# NightLight.net
KiCad netlist of a schematic drawn in EAGLE
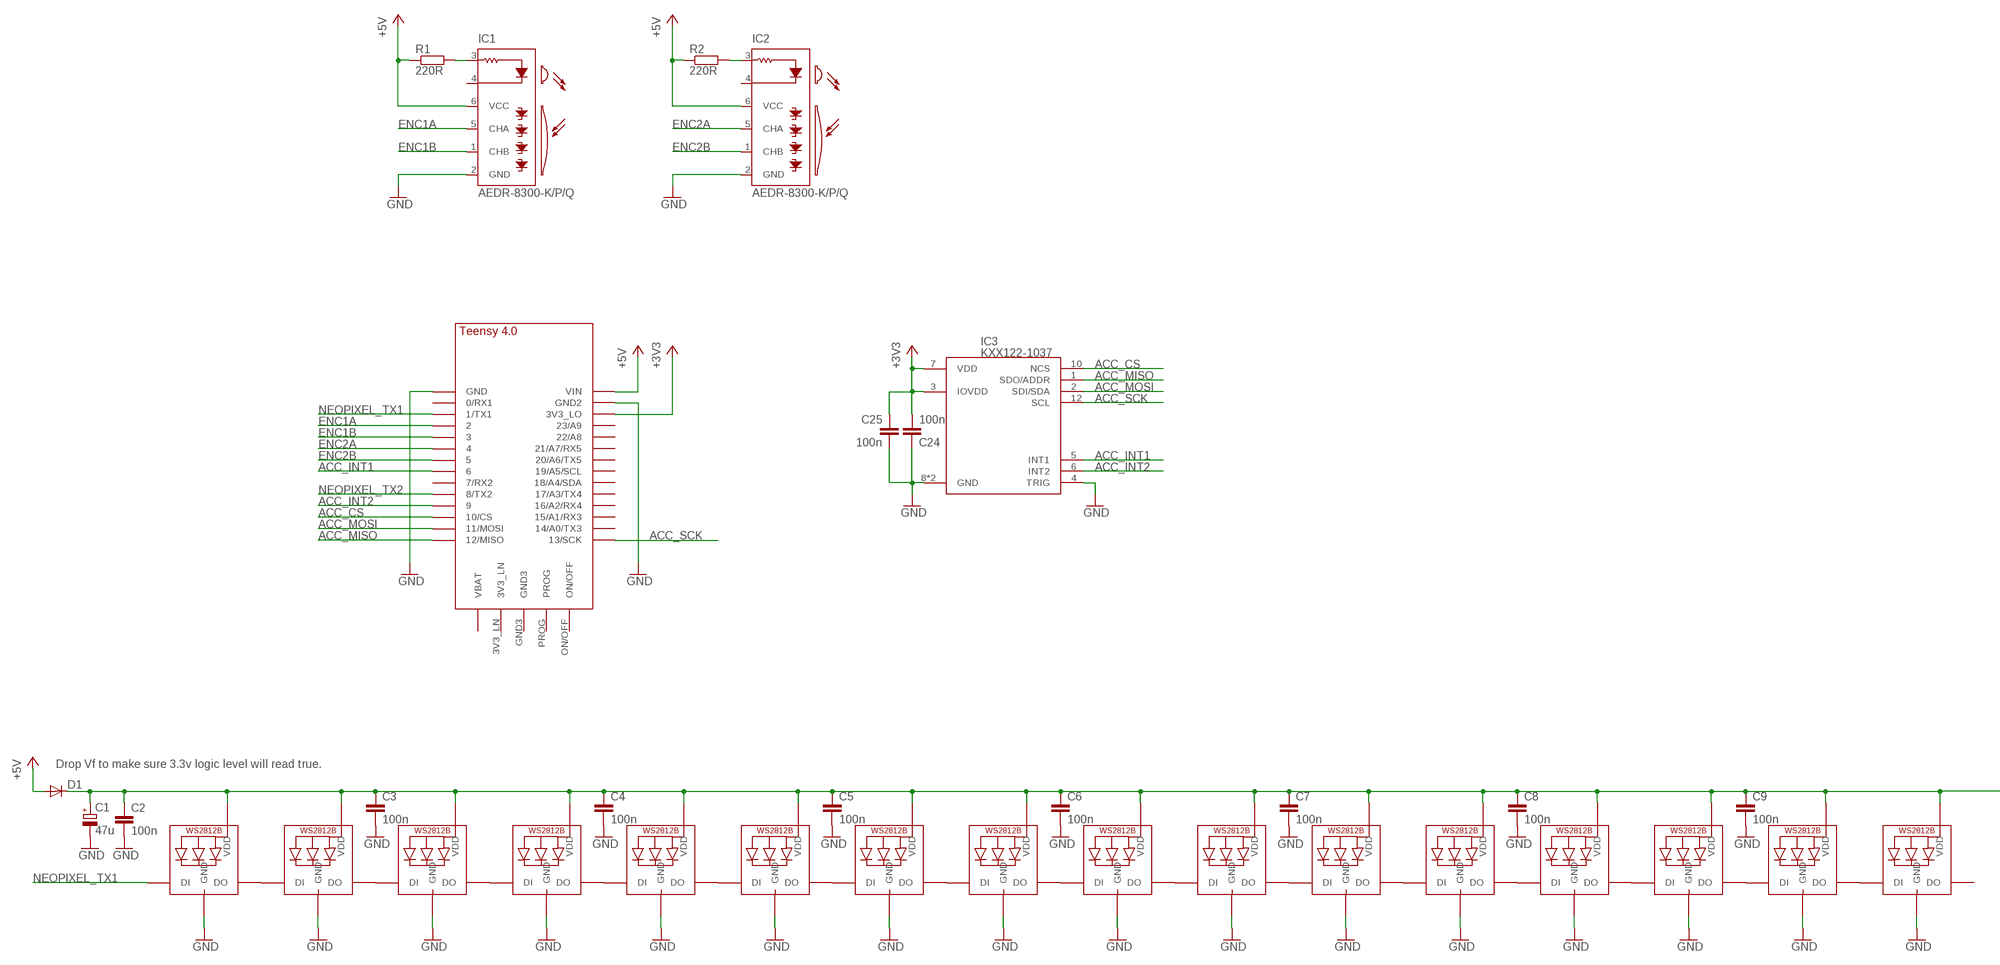
[diagram p0: schematic, sheet 1, part 1 of 2]
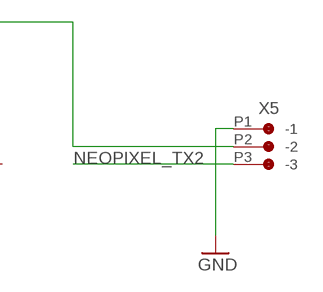
[diagram p1: schematic, sheet 1, part 2 of 2]

(export (version "E")
  (design (tool "Eeschema 10.0.6"))
  (components
    (comp (ref "C1")
      (value "47u")
      (footprint "eagle-import:CPOL-5")
      (libsource (lib "eagle-import") (part "CPOL-EU153CLV-0505"))
    )
    (comp (ref "C2")
      (value "100n")
      (footprint "eagle-import:C0603")
      (libsource (lib "eagle-import") (part "Rebel_15457297_C-EUC0603"))
    )
    (comp (ref "C3")
      (value "100n")
      (footprint "eagle-import:C0603")
      (libsource (lib "eagle-import") (part "Rebel_15457297_C-EUC0603"))
    )
    (comp (ref "C4")
      (value "100n")
      (footprint "eagle-import:C0603")
      (libsource (lib "eagle-import") (part "Rebel_15457297_C-EUC0603"))
    )
    (comp (ref "C5")
      (value "100n")
      (footprint "eagle-import:C0603")
      (libsource (lib "eagle-import") (part "Rebel_15457297_C-EUC0603"))
    )
    (comp (ref "C6")
      (value "100n")
      (footprint "eagle-import:C0603")
      (libsource (lib "eagle-import") (part "Rebel_15457297_C-EUC0603"))
    )
    (comp (ref "C7")
      (value "100n")
      (footprint "eagle-import:C0603")
      (libsource (lib "eagle-import") (part "Rebel_15457297_C-EUC0603"))
    )
    (comp (ref "C8")
      (value "100n")
      (footprint "eagle-import:C0603")
      (libsource (lib "eagle-import") (part "Rebel_15457297_C-EUC0603"))
    )
    (comp (ref "C9")
      (value "100n")
      (footprint "eagle-import:C0603")
      (libsource (lib "eagle-import") (part "Rebel_15457297_C-EUC0603"))
    )
    (comp (ref "C24")
      (value "100n")
      (footprint "eagle-import:C0603")
      (libsource (lib "eagle-import") (part "C-EUC0603"))
    )
    (comp (ref "C25")
      (value "100n")
      (footprint "eagle-import:C0603")
      (libsource (lib "eagle-import") (part "C-EUC0603"))
    )
    (comp (ref "D1")
      (value "DIODE1N4001")
      (footprint "eagle-import:DIODE-1N4001")
      (libsource (lib "eagle-import") (part "DIODE1N4001"))
    )
    (comp (ref "IC1")
      (value "AEDR-8300-K/P/Q")
      (footprint "eagle-import:AEDR-8300")
      (fields (field (name "MF") "AGILENT TECHNOLOGIES") (field (name "MPN") "AEDR-8300-1P2"))
      (libsource (lib "eagle-import") (part "AEDR-8300-K/P/Q"))
    )
    (comp (ref "IC2")
      (value "AEDR-8300-K/P/Q")
      (footprint "eagle-import:AEDR-8300")
      (fields (field (name "MF") "AGILENT TECHNOLOGIES") (field (name "MPN") "AEDR-8300-1P2"))
      (libsource (lib "eagle-import") (part "AEDR-8300-K/P/Q"))
    )
    (comp (ref "IC3")
      (value "KXX122-1037")
      (footprint "eagle-import:LGA16R50P4X4_200X200X100")
      (libsource (lib "eagle-import") (part "KXX122-1037"))
    )
    (comp (ref "LED1")
      (value "WS2812B5050")
      (footprint "eagle-import:WS2812B")
      (libsource (lib "eagle-import") (part "WS2812B5050"))
    )
    (comp (ref "LED2")
      (value "WS2812B5050")
      (footprint "eagle-import:WS2812B")
      (libsource (lib "eagle-import") (part "WS2812B5050"))
    )
    (comp (ref "LED3")
      (value "WS2812B5050")
      (footprint "eagle-import:WS2812B")
      (libsource (lib "eagle-import") (part "WS2812B5050"))
    )
    (comp (ref "LED4")
      (value "WS2812B5050")
      (footprint "eagle-import:WS2812B")
      (libsource (lib "eagle-import") (part "WS2812B5050"))
    )
    (comp (ref "LED5")
      (value "WS2812B5050")
      (footprint "eagle-import:WS2812B")
      (libsource (lib "eagle-import") (part "WS2812B5050"))
    )
    (comp (ref "LED6")
      (value "WS2812B5050")
      (footprint "eagle-import:WS2812B")
      (libsource (lib "eagle-import") (part "WS2812B5050"))
    )
    (comp (ref "LED7")
      (value "WS2812B5050")
      (footprint "eagle-import:WS2812B")
      (libsource (lib "eagle-import") (part "WS2812B5050"))
    )
    (comp (ref "LED8")
      (value "WS2812B5050")
      (footprint "eagle-import:WS2812B")
      (libsource (lib "eagle-import") (part "WS2812B5050"))
    )
    (comp (ref "LED9")
      (value "WS2812B5050")
      (footprint "eagle-import:WS2812B")
      (libsource (lib "eagle-import") (part "WS2812B5050"))
    )
    (comp (ref "LED10")
      (value "WS2812B5050")
      (footprint "eagle-import:WS2812B")
      (libsource (lib "eagle-import") (part "WS2812B5050"))
    )
    (comp (ref "LED11")
      (value "WS2812B5050")
      (footprint "eagle-import:WS2812B")
      (libsource (lib "eagle-import") (part "WS2812B5050"))
    )
    (comp (ref "LED12")
      (value "WS2812B5050")
      (footprint "eagle-import:WS2812B")
      (libsource (lib "eagle-import") (part "WS2812B5050"))
    )
    (comp (ref "LED13")
      (value "WS2812B5050")
      (footprint "eagle-import:WS2812B")
      (libsource (lib "eagle-import") (part "WS2812B5050"))
    )
    (comp (ref "LED14")
      (value "WS2812B5050")
      (footprint "eagle-import:WS2812B")
      (libsource (lib "eagle-import") (part "WS2812B5050"))
    )
    (comp (ref "LED15")
      (value "WS2812B5050")
      (footprint "eagle-import:WS2812B")
      (libsource (lib "eagle-import") (part "WS2812B5050"))
    )
    (comp (ref "LED16")
      (value "WS2812B5050")
      (footprint "eagle-import:WS2812B")
      (libsource (lib "eagle-import") (part "WS2812B5050"))
    )
    (comp (ref "R1")
      (value "220R")
      (footprint "eagle-import:0603")
      (libsource (lib "eagle-import") (part "R-EU_0603"))
    )
    (comp (ref "R2")
      (value "220R")
      (footprint "eagle-import:0603")
      (libsource (lib "eagle-import") (part "R-EU_0603"))
    )
    (comp (ref "U$1")
      (value "TEENSY_4.0-BASIC")
      (footprint "eagle-import:TEENSY_4.0-BASIC")
      (libsource (lib "eagle-import") (part "TEENSY_4.0-BASIC"))
    )
    (comp (ref "X5")
      (value "CON-JST_PH_3W")
      (footprint "eagle-import:CON-JST_PH_3W")
      (libsource (lib "eagle-import") (part "CON-JST_PH_3W"))
    )
  )
  (nets
    (net (code "1") (name "+3V3") (class "Default")
      (node (ref "C24") (pin "2") (pinfunction "2_2") (pintype "passive"))
      (node (ref "C25") (pin "1") (pinfunction "1_1") (pintype "passive"))
      (node (ref "IC3") (pin "3") (pinfunction "IOVDD_3") (pintype "bidirectional"))
      (node (ref "IC3") (pin "7") (pinfunction "VDD_7") (pintype "bidirectional"))
      (node (ref "U$1") (pin "3V3_LO") (pinfunction "3V3_LO_3V3_LO") (pintype "bidirectional"))
    )
    (net (code "2") (name "+5V") (class "Default")
      (node (ref "D1") (pin "A") (pinfunction "A_A") (pintype "passive"))
      (node (ref "IC1") (pin "6") (pinfunction "VCC_6") (pintype "passive"))
      (node (ref "IC2") (pin "6") (pinfunction "VCC_6") (pintype "passive"))
      (node (ref "R1") (pin "1") (pinfunction "1_1") (pintype "passive"))
      (node (ref "R2") (pin "1") (pinfunction "1_1") (pintype "passive"))
      (node (ref "U$1") (pin "VIN") (pinfunction "VIN_VIN") (pintype "bidirectional"))
    )
    (net (code "3") (name "/ACC_CS") (class "Default")
      (node (ref "IC3") (pin "10") (pinfunction "NCS_10") (pintype "bidirectional"))
      (node (ref "U$1") (pin "10/CS") (pinfunction "10/CS_10/CS") (pintype "bidirectional"))
    )
    (net (code "4") (name "/ACC_INT1") (class "Default")
      (node (ref "IC3") (pin "5") (pinfunction "INT1_5") (pintype "bidirectional"))
      (node (ref "U$1") (pin "6") (pinfunction "6_6") (pintype "bidirectional"))
    )
    (net (code "5") (name "/ACC_INT2") (class "Default")
      (node (ref "IC3") (pin "6") (pinfunction "INT2_6") (pintype "bidirectional"))
      (node (ref "U$1") (pin "9/CS") (pinfunction "9_9/CS") (pintype "bidirectional"))
    )
    (net (code "6") (name "/ACC_MISO") (class "Default")
      (node (ref "IC3") (pin "1") (pinfunction "SDO/ADDR_1") (pintype "bidirectional"))
      (node (ref "U$1") (pin "12/MISO") (pinfunction "12/MISO_12/MISO") (pintype "bidirectional"))
    )
    (net (code "7") (name "/ACC_MOSI") (class "Default")
      (node (ref "IC3") (pin "2") (pinfunction "SDI/SDA_2") (pintype "bidirectional"))
      (node (ref "U$1") (pin "11/MOSI") (pinfunction "11/MOSI_11/MOSI") (pintype "bidirectional"))
    )
    (net (code "8") (name "/ACC_SCK") (class "Default")
      (node (ref "IC3") (pin "12") (pinfunction "SCL_12") (pintype "bidirectional"))
      (node (ref "U$1") (pin "13/SCK") (pinfunction "13/SCK_13/SCK") (pintype "bidirectional"))
    )
    (net (code "9") (name "/ENC1A") (class "Default")
      (node (ref "IC1") (pin "5") (pinfunction "CHA_5") (pintype "passive"))
      (node (ref "U$1") (pin "2") (pinfunction "2_2") (pintype "bidirectional"))
    )
    (net (code "10") (name "/ENC1B") (class "Default")
      (node (ref "IC1") (pin "1") (pinfunction "CHB_1") (pintype "passive"))
      (node (ref "U$1") (pin "3/CANTX") (pinfunction "3_3/CANTX") (pintype "bidirectional"))
    )
    (net (code "11") (name "/ENC2A") (class "Default")
      (node (ref "IC2") (pin "5") (pinfunction "CHA_5") (pintype "passive"))
      (node (ref "U$1") (pin "4/CANRX") (pinfunction "4_4/CANRX") (pintype "bidirectional"))
    )
    (net (code "12") (name "/ENC2B") (class "Default")
      (node (ref "IC2") (pin "1") (pinfunction "CHB_1") (pintype "passive"))
      (node (ref "U$1") (pin "5") (pinfunction "5_5") (pintype "bidirectional"))
    )
    (net (code "13") (name "/NEOPIXEL_TX1") (class "Default")
      (node (ref "LED1") (pin "4-DIN") (pinfunction "DI_4-DIN") (pintype "input"))
      (node (ref "U$1") (pin "1/TX") (pinfunction "1/TX1_1/TX") (pintype "bidirectional"))
    )
    (net (code "14") (name "/NEOPIXEL_TX2") (class "Default")
      (node (ref "U$1") (pin "8") (pinfunction "8/TX2_8") (pintype "bidirectional"))
      (node (ref "X5") (pin "P3") (pinfunction "-3_P3") (pintype "bidirectional"))
    )
    (net (code "15") (name "GND") (class "Default")
      (node (ref "C1") (pin "-") (pinfunction "-_-") (pintype "passive"))
      (node (ref "C2") (pin "2") (pinfunction "2_2") (pintype "passive"))
      (node (ref "C24") (pin "1") (pinfunction "1_1") (pintype "passive"))
      (node (ref "C25") (pin "2") (pinfunction "2_2") (pintype "passive"))
      (node (ref "C3") (pin "2") (pinfunction "2_2") (pintype "passive"))
      (node (ref "C4") (pin "2") (pinfunction "2_2") (pintype "passive"))
      (node (ref "C5") (pin "2") (pinfunction "2_2") (pintype "passive"))
      (node (ref "C6") (pin "2") (pinfunction "2_2") (pintype "passive"))
      (node (ref "C7") (pin "2") (pinfunction "2_2") (pintype "passive"))
      (node (ref "C8") (pin "2") (pinfunction "2_2") (pintype "passive"))
      (node (ref "C9") (pin "2") (pinfunction "2_2") (pintype "passive"))
      (node (ref "IC1") (pin "2") (pinfunction "GND_2") (pintype "passive"))
      (node (ref "IC2") (pin "2") (pinfunction "GND_2") (pintype "passive"))
      (node (ref "IC3") (pin "4") (pinfunction "TRIG_4") (pintype "bidirectional"))
      (node (ref "IC3") (pin "8") (pinfunction "GND_8") (pintype "bidirectional"))
      (node (ref "IC3") (pin "9") (pinfunction "GND_9") (pintype "bidirectional"))
      (node (ref "LED1") (pin "3-GND") (pinfunction "GND_3-GND") (pintype "power_in"))
      (node (ref "LED10") (pin "3-GND") (pinfunction "GND_3-GND") (pintype "power_in"))
      (node (ref "LED11") (pin "3-GND") (pinfunction "GND_3-GND") (pintype "power_in"))
      (node (ref "LED12") (pin "3-GND") (pinfunction "GND_3-GND") (pintype "power_in"))
      (node (ref "LED13") (pin "3-GND") (pinfunction "GND_3-GND") (pintype "power_in"))
      (node (ref "LED14") (pin "3-GND") (pinfunction "GND_3-GND") (pintype "power_in"))
      (node (ref "LED15") (pin "3-GND") (pinfunction "GND_3-GND") (pintype "power_in"))
      (node (ref "LED16") (pin "3-GND") (pinfunction "GND_3-GND") (pintype "power_in"))
      (node (ref "LED2") (pin "3-GND") (pinfunction "GND_3-GND") (pintype "power_in"))
      (node (ref "LED3") (pin "3-GND") (pinfunction "GND_3-GND") (pintype "power_in"))
      (node (ref "LED4") (pin "3-GND") (pinfunction "GND_3-GND") (pintype "power_in"))
      (node (ref "LED5") (pin "3-GND") (pinfunction "GND_3-GND") (pintype "power_in"))
      (node (ref "LED6") (pin "3-GND") (pinfunction "GND_3-GND") (pintype "power_in"))
      (node (ref "LED7") (pin "3-GND") (pinfunction "GND_3-GND") (pintype "power_in"))
      (node (ref "LED8") (pin "3-GND") (pinfunction "GND_3-GND") (pintype "power_in"))
      (node (ref "LED9") (pin "3-GND") (pinfunction "GND_3-GND") (pintype "power_in"))
      (node (ref "U$1") (pin "GND") (pinfunction "GND_GND") (pintype "bidirectional"))
      (node (ref "U$1") (pin "GND2") (pinfunction "GND2_GND2") (pintype "bidirectional"))
      (node (ref "X5") (pin "P1") (pinfunction "-1_P1") (pintype "bidirectional"))
    )
    (net (code "16") (name "Net-(IC1A-A)") (class "Default")
      (node (ref "IC1") (pin "3") (pinfunction "A_3") (pintype "passive"))
      (node (ref "R1") (pin "2") (pinfunction "2_2") (pintype "passive"))
    )
    (net (code "17") (name "Net-(IC2A-A)") (class "Default")
      (node (ref "IC2") (pin "3") (pinfunction "A_3") (pintype "passive"))
      (node (ref "R2") (pin "2") (pinfunction "2_2") (pintype "passive"))
    )
    (net (code "18") (name "Net-(LED1-DO)") (class "Default")
      (node (ref "LED1") (pin "2-DOUT") (pinfunction "DO_2-DOUT") (pintype "output"))
      (node (ref "LED2") (pin "4-DIN") (pinfunction "DI_4-DIN") (pintype "input"))
    )
    (net (code "19") (name "Net-(LED1-VDD)") (class "Default")
      (node (ref "C1") (pin "+") (pinfunction "+_+") (pintype "passive"))
      (node (ref "C2") (pin "1") (pinfunction "1_1") (pintype "passive"))
      (node (ref "C3") (pin "1") (pinfunction "1_1") (pintype "passive"))
      (node (ref "C4") (pin "1") (pinfunction "1_1") (pintype "passive"))
      (node (ref "C5") (pin "1") (pinfunction "1_1") (pintype "passive"))
      (node (ref "C6") (pin "1") (pinfunction "1_1") (pintype "passive"))
      (node (ref "C7") (pin "1") (pinfunction "1_1") (pintype "passive"))
      (node (ref "C8") (pin "1") (pinfunction "1_1") (pintype "passive"))
      (node (ref "C9") (pin "1") (pinfunction "1_1") (pintype "passive"))
      (node (ref "D1") (pin "C") (pinfunction "C_C") (pintype "passive"))
      (node (ref "LED1") (pin "1-VDD") (pinfunction "VDD_1-VDD") (pintype "power_in"))
      (node (ref "LED10") (pin "1-VDD") (pinfunction "VDD_1-VDD") (pintype "power_in"))
      (node (ref "LED11") (pin "1-VDD") (pinfunction "VDD_1-VDD") (pintype "power_in"))
      (node (ref "LED12") (pin "1-VDD") (pinfunction "VDD_1-VDD") (pintype "power_in"))
      (node (ref "LED13") (pin "1-VDD") (pinfunction "VDD_1-VDD") (pintype "power_in"))
      (node (ref "LED14") (pin "1-VDD") (pinfunction "VDD_1-VDD") (pintype "power_in"))
      (node (ref "LED15") (pin "1-VDD") (pinfunction "VDD_1-VDD") (pintype "power_in"))
      (node (ref "LED16") (pin "1-VDD") (pinfunction "VDD_1-VDD") (pintype "power_in"))
      (node (ref "LED2") (pin "1-VDD") (pinfunction "VDD_1-VDD") (pintype "power_in"))
      (node (ref "LED3") (pin "1-VDD") (pinfunction "VDD_1-VDD") (pintype "power_in"))
      (node (ref "LED4") (pin "1-VDD") (pinfunction "VDD_1-VDD") (pintype "power_in"))
      (node (ref "LED5") (pin "1-VDD") (pinfunction "VDD_1-VDD") (pintype "power_in"))
      (node (ref "LED6") (pin "1-VDD") (pinfunction "VDD_1-VDD") (pintype "power_in"))
      (node (ref "LED7") (pin "1-VDD") (pinfunction "VDD_1-VDD") (pintype "power_in"))
      (node (ref "LED8") (pin "1-VDD") (pinfunction "VDD_1-VDD") (pintype "power_in"))
      (node (ref "LED9") (pin "1-VDD") (pinfunction "VDD_1-VDD") (pintype "power_in"))
      (node (ref "X5") (pin "P2") (pinfunction "-2_P2") (pintype "bidirectional"))
    )
    (net (code "20") (name "Net-(LED2-DO)") (class "Default")
      (node (ref "LED2") (pin "2-DOUT") (pinfunction "DO_2-DOUT") (pintype "output"))
      (node (ref "LED3") (pin "4-DIN") (pinfunction "DI_4-DIN") (pintype "input"))
    )
    (net (code "21") (name "Net-(LED3-DO)") (class "Default")
      (node (ref "LED3") (pin "2-DOUT") (pinfunction "DO_2-DOUT") (pintype "output"))
      (node (ref "LED4") (pin "4-DIN") (pinfunction "DI_4-DIN") (pintype "input"))
    )
    (net (code "22") (name "Net-(LED4-DO)") (class "Default")
      (node (ref "LED4") (pin "2-DOUT") (pinfunction "DO_2-DOUT") (pintype "output"))
      (node (ref "LED5") (pin "4-DIN") (pinfunction "DI_4-DIN") (pintype "input"))
    )
    (net (code "23") (name "Net-(LED5-DO)") (class "Default")
      (node (ref "LED5") (pin "2-DOUT") (pinfunction "DO_2-DOUT") (pintype "output"))
      (node (ref "LED6") (pin "4-DIN") (pinfunction "DI_4-DIN") (pintype "input"))
    )
    (net (code "24") (name "Net-(LED6-DO)") (class "Default")
      (node (ref "LED6") (pin "2-DOUT") (pinfunction "DO_2-DOUT") (pintype "output"))
      (node (ref "LED7") (pin "4-DIN") (pinfunction "DI_4-DIN") (pintype "input"))
    )
    (net (code "25") (name "Net-(LED7-DO)") (class "Default")
      (node (ref "LED7") (pin "2-DOUT") (pinfunction "DO_2-DOUT") (pintype "output"))
      (node (ref "LED8") (pin "4-DIN") (pinfunction "DI_4-DIN") (pintype "input"))
    )
    (net (code "26") (name "Net-(LED8-DO)") (class "Default")
      (node (ref "LED8") (pin "2-DOUT") (pinfunction "DO_2-DOUT") (pintype "output"))
      (node (ref "LED9") (pin "4-DIN") (pinfunction "DI_4-DIN") (pintype "input"))
    )
    (net (code "27") (name "Net-(LED10-DI)") (class "Default")
      (node (ref "LED10") (pin "4-DIN") (pinfunction "DI_4-DIN") (pintype "input"))
      (node (ref "LED9") (pin "2-DOUT") (pinfunction "DO_2-DOUT") (pintype "output"))
    )
    (net (code "28") (name "Net-(LED10-DO)") (class "Default")
      (node (ref "LED10") (pin "2-DOUT") (pinfunction "DO_2-DOUT") (pintype "output"))
      (node (ref "LED11") (pin "4-DIN") (pinfunction "DI_4-DIN") (pintype "input"))
    )
    (net (code "29") (name "Net-(LED11-DO)") (class "Default")
      (node (ref "LED11") (pin "2-DOUT") (pinfunction "DO_2-DOUT") (pintype "output"))
      (node (ref "LED12") (pin "4-DIN") (pinfunction "DI_4-DIN") (pintype "input"))
    )
    (net (code "30") (name "Net-(LED12-DO)") (class "Default")
      (node (ref "LED12") (pin "2-DOUT") (pinfunction "DO_2-DOUT") (pintype "output"))
      (node (ref "LED13") (pin "4-DIN") (pinfunction "DI_4-DIN") (pintype "input"))
    )
    (net (code "31") (name "Net-(LED13-DO)") (class "Default")
      (node (ref "LED13") (pin "2-DOUT") (pinfunction "DO_2-DOUT") (pintype "output"))
      (node (ref "LED14") (pin "4-DIN") (pinfunction "DI_4-DIN") (pintype "input"))
    )
    (net (code "32") (name "Net-(LED14-DO)") (class "Default")
      (node (ref "LED14") (pin "2-DOUT") (pinfunction "DO_2-DOUT") (pintype "output"))
      (node (ref "LED15") (pin "4-DIN") (pinfunction "DI_4-DIN") (pintype "input"))
    )
    (net (code "33") (name "Net-(LED15-DO)") (class "Default")
      (node (ref "LED15") (pin "2-DOUT") (pinfunction "DO_2-DOUT") (pintype "output"))
      (node (ref "LED16") (pin "4-DIN") (pinfunction "DI_4-DIN") (pintype "input"))
    )
    (net (code "34") (name "unconnected-(IC1A-C-Pad4)") (class "Default")
      (node (ref "IC1") (pin "4") (pinfunction "C_4") (pintype "passive"))
    )
    (net (code "35") (name "unconnected-(IC2A-C-Pad4)") (class "Default")
      (node (ref "IC2") (pin "4") (pinfunction "C_4") (pintype "passive"))
    )
    (net (code "36") (name "unconnected-(LED16-DO-Pad2-DOUT)") (class "Default")
      (node (ref "LED16") (pin "2-DOUT") (pinfunction "DO_2-DOUT") (pintype "output"))
    )
    (net (code "37") (name "unconnected-(U$1-0{slash}RX1-Pad0{slash}RX)") (class "Default")
      (node (ref "U$1") (pin "0/RX") (pinfunction "0/RX1_0/RX") (pintype "bidirectional"))
    )
    (net (code "38") (name "unconnected-(U$1-7{slash}RX2-Pad7)") (class "Default")
      (node (ref "U$1") (pin "7") (pinfunction "7/RX2_7") (pintype "bidirectional"))
    )
    (net (code "39") (name "unconnected-(U$1-14{slash}A0{slash}TX3-Pad14{slash}A0)") (class "Default")
      (node (ref "U$1") (pin "14/A0") (pinfunction "14/A0/TX3_14/A0") (pintype "bidirectional"))
    )
    (net (code "40") (name "unconnected-(U$1-15{slash}A1{slash}RX3-Pad15{slash}A1)") (class "Default")
      (node (ref "U$1") (pin "15/A1") (pinfunction "15/A1/RX3_15/A1") (pintype "bidirectional"))
    )
    (net (code "41") (name "unconnected-(U$1-16{slash}A2{slash}RX4-Pad16{slash}A2)") (class "Default")
      (node (ref "U$1") (pin "16/A2") (pinfunction "16/A2/RX4_16/A2") (pintype "bidirectional"))
    )
    (net (code "42") (name "unconnected-(U$1-17{slash}A3{slash}TX4-Pad17{slash}A3)") (class "Default")
      (node (ref "U$1") (pin "17/A3") (pinfunction "17/A3/TX4_17/A3") (pintype "bidirectional"))
    )
    (net (code "43") (name "unconnected-(U$1-20{slash}A6{slash}TX5-Pad20{slash}A6)") (class "Default")
      (node (ref "U$1") (pin "20/A6") (pinfunction "20/A6/TX5_20/A6") (pintype "bidirectional"))
    )
    (net (code "44") (name "unconnected-(U$1-21{slash}A7{slash}RX5-Pad21{slash}A7)") (class "Default")
      (node (ref "U$1") (pin "21/A7") (pinfunction "21/A7/RX5_21/A7") (pintype "bidirectional"))
    )
    (net (code "45") (name "unconnected-(U$1-Pad3V3_LN)") (class "Default")
      (node (ref "U$1") (pin "3V3_LN") (pinfunction "3V3_LN_3V3_LN") (pintype "bidirectional"))
    )
    (net (code "46") (name "unconnected-(U$1-Pad18{slash}A4{slash}SDA)") (class "Default")
      (node (ref "U$1") (pin "18/A4/SDA") (pinfunction "18/A4/SDA_18/A4/SDA") (pintype "bidirectional"))
    )
    (net (code "47") (name "unconnected-(U$1-Pad19{slash}A5{slash}SCL)") (class "Default")
      (node (ref "U$1") (pin "19/A5/SCL") (pinfunction "19/A5/SCL_19/A5/SCL") (pintype "bidirectional"))
    )
    (net (code "48") (name "unconnected-(U$1-Pad22{slash}A8)") (class "Default")
      (node (ref "U$1") (pin "22/A8") (pinfunction "22/A8_22/A8") (pintype "bidirectional"))
    )
    (net (code "49") (name "unconnected-(U$1-Pad23{slash}A9)") (class "Default")
      (node (ref "U$1") (pin "23/A9") (pinfunction "23/A9_23/A9") (pintype "bidirectional"))
    )
    (net (code "50") (name "unconnected-(U$1-PadGND3)") (class "Default")
      (node (ref "U$1") (pin "GND3") (pinfunction "GND3_GND3") (pintype "bidirectional"))
    )
    (net (code "51") (name "unconnected-(U$1-PadON{slash}OFF)") (class "Default")
      (node (ref "U$1") (pin "ON/OFF") (pinfunction "ON/OFF_ON/OFF") (pintype "bidirectional"))
    )
    (net (code "52") (name "unconnected-(U$1-PadPROG)") (class "Default")
      (node (ref "U$1") (pin "PROG") (pinfunction "PROG_PROG") (pintype "bidirectional"))
    )
    (net (code "53") (name "unconnected-(U$1-VBAT-PadVBAT\\)") (class "Default")
      (node (ref "U$1") (pin "VBAT\\") (pinfunction "VBAT_VBAT\\") (pintype "bidirectional"))
    )
  )
)
